# Driver_Motor_opto_bawah.net
KiCad netlist of a schematic drawn in EAGLE
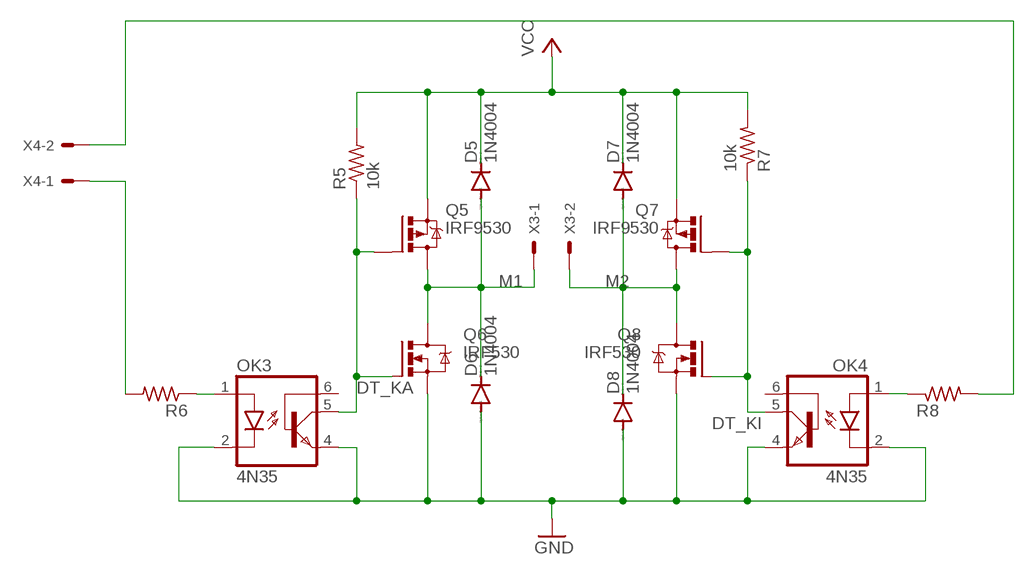
[diagram p0: schematic, sheet 1]

(export (version "E")
  (design (tool "Eeschema 10.0.6"))
  (components
    (comp (ref "D5")
      (value "1N4004")
      (footprint "eagle-import:DO41-10")
      (libsource (lib "eagle-import") (part "1N4004"))
    )
    (comp (ref "D6")
      (value "1N4004")
      (footprint "eagle-import:DO41-10")
      (libsource (lib "eagle-import") (part "1N4004"))
    )
    (comp (ref "D7")
      (value "1N4004")
      (footprint "eagle-import:DO41-10")
      (libsource (lib "eagle-import") (part "1N4004"))
    )
    (comp (ref "D8")
      (value "1N4004")
      (footprint "eagle-import:DO41-10")
      (libsource (lib "eagle-import") (part "1N4004"))
    )
    (comp (ref "OK3")
      (value "4N35")
      (footprint "eagle-import:DIL06")
      (fields (field (name "MF") "FAIRCHILD SEMICONDUCTOR"))
      (libsource (lib "eagle-import") (part "4N35"))
    )
    (comp (ref "OK4")
      (value "4N35")
      (footprint "eagle-import:DIL06")
      (fields (field (name "MF") "FAIRCHILD SEMICONDUCTOR"))
      (libsource (lib "eagle-import") (part "4N35"))
    )
    (comp (ref "Q5")
      (value "IRF9530")
      (footprint "eagle-import:TO220BV")
      (libsource (lib "eagle-import") (part "IRF9530"))
    )
    (comp (ref "Q6")
      (value "IRF530")
      (footprint "eagle-import:TO220BV")
      (libsource (lib "eagle-import") (part "IRF530"))
    )
    (comp (ref "Q7")
      (value "IRF9530")
      (footprint "eagle-import:TO220BV")
      (libsource (lib "eagle-import") (part "IRF9530"))
    )
    (comp (ref "Q8")
      (value "IRF530")
      (footprint "eagle-import:TO220BV")
      (libsource (lib "eagle-import") (part "IRF530"))
    )
    (comp (ref "R5")
      (value "10k")
      (footprint "eagle-import:0207_10")
      (libsource (lib "eagle-import") (part "R-US_0207/10"))
    )
    (comp (ref "R6")
      (value "R-US_0207/10")
      (footprint "eagle-import:0207_10")
      (libsource (lib "eagle-import") (part "R-US_0207/10"))
    )
    (comp (ref "R7")
      (value "10k")
      (footprint "eagle-import:0207_10")
      (libsource (lib "eagle-import") (part "R-US_0207/10"))
    )
    (comp (ref "R8")
      (value "R-US_0207/10")
      (footprint "eagle-import:0207_10")
      (libsource (lib "eagle-import") (part "R-US_0207/10"))
    )
    (comp (ref "X3")
      (value "22-23-2021")
      (footprint "eagle-import:22-23-2021")
      (fields (field (name "MF") "MOLEX"))
      (libsource (lib "eagle-import") (part "22-23-2021"))
    )
    (comp (ref "X4")
      (value "22-23-2021")
      (footprint "eagle-import:22-23-2021")
      (fields (field (name "MF") "MOLEX"))
      (libsource (lib "eagle-import") (part "22-23-2021"))
    )
  )
  (nets
    (net (code "1") (name "/DT_KA") (class "Default")
      (node (ref "OK3") (pin "5") (pinfunction "COL_5") (pintype "passive"))
      (node (ref "Q5") (pin "G") (pinfunction "G_G") (pintype "passive"))
      (node (ref "Q6") (pin "G") (pinfunction "G_G") (pintype "passive"))
      (node (ref "R5") (pin "1") (pinfunction "1_1") (pintype "passive"))
    )
    (net (code "2") (name "/DT_KI") (class "Default")
      (node (ref "OK4") (pin "5") (pinfunction "COL_5") (pintype "passive"))
      (node (ref "Q7") (pin "G") (pinfunction "G_G") (pintype "passive"))
      (node (ref "Q8") (pin "G") (pinfunction "G_G") (pintype "passive"))
      (node (ref "R7") (pin "1") (pinfunction "1_1") (pintype "passive"))
    )
    (net (code "3") (name "/M1") (class "Default")
      (node (ref "D5") (pin "A") (pinfunction "A_A") (pintype "passive"))
      (node (ref "D6") (pin "C") (pinfunction "C_C") (pintype "passive"))
      (node (ref "Q5") (pin "D") (pinfunction "D_D") (pintype "passive"))
      (node (ref "Q6") (pin "D") (pinfunction "D_D") (pintype "passive"))
      (node (ref "X3") (pin "1") (pinfunction "S_1") (pintype "passive"))
    )
    (net (code "4") (name "/M2") (class "Default")
      (node (ref "D7") (pin "A") (pinfunction "A_A") (pintype "passive"))
      (node (ref "D8") (pin "C") (pinfunction "C_C") (pintype "passive"))
      (node (ref "Q7") (pin "D") (pinfunction "D_D") (pintype "passive"))
      (node (ref "Q8") (pin "D") (pinfunction "D_D") (pintype "passive"))
      (node (ref "X3") (pin "2") (pinfunction "S_2") (pintype "passive"))
    )
    (net (code "5") (name "GND") (class "Default")
      (node (ref "D6") (pin "A") (pinfunction "A_A") (pintype "passive"))
      (node (ref "D8") (pin "A") (pinfunction "A_A") (pintype "passive"))
      (node (ref "OK3") (pin "2") (pinfunction "C_2") (pintype "passive"))
      (node (ref "OK3") (pin "4") (pinfunction "EMI_4") (pintype "passive"))
      (node (ref "OK4") (pin "2") (pinfunction "C_2") (pintype "passive"))
      (node (ref "OK4") (pin "4") (pinfunction "EMI_4") (pintype "passive"))
      (node (ref "Q6") (pin "S") (pinfunction "S_S") (pintype "passive"))
      (node (ref "Q8") (pin "S") (pinfunction "S_S") (pintype "passive"))
    )
    (net (code "6") (name "Net-(OK3-A)") (class "Default")
      (node (ref "OK3") (pin "1") (pinfunction "A_1") (pintype "passive"))
      (node (ref "R6") (pin "1") (pinfunction "1_1") (pintype "passive"))
    )
    (net (code "7") (name "Net-(OK4-A)") (class "Default")
      (node (ref "OK4") (pin "1") (pinfunction "A_1") (pintype "passive"))
      (node (ref "R8") (pin "1") (pinfunction "1_1") (pintype "passive"))
    )
    (net (code "8") (name "Net-(X4A-S)") (class "Default")
      (node (ref "R6") (pin "2") (pinfunction "2_2") (pintype "passive"))
      (node (ref "X4") (pin "1") (pinfunction "S_1") (pintype "passive"))
    )
    (net (code "9") (name "Net-(X4B-S)") (class "Default")
      (node (ref "R8") (pin "2") (pinfunction "2_2") (pintype "passive"))
      (node (ref "X4") (pin "2") (pinfunction "S_2") (pintype "passive"))
    )
    (net (code "10") (name "VCC") (class "Default")
      (node (ref "D5") (pin "C") (pinfunction "C_C") (pintype "passive"))
      (node (ref "D7") (pin "C") (pinfunction "C_C") (pintype "passive"))
      (node (ref "Q5") (pin "S") (pinfunction "S_S") (pintype "passive"))
      (node (ref "Q7") (pin "S") (pinfunction "S_S") (pintype "passive"))
      (node (ref "R5") (pin "2") (pinfunction "2_2") (pintype "passive"))
      (node (ref "R7") (pin "2") (pinfunction "2_2") (pintype "passive"))
    )
    (net (code "11") (name "unconnected-(OK3-BAS-Pad6)") (class "Default")
      (node (ref "OK3") (pin "6") (pinfunction "BAS_6") (pintype "passive"))
    )
    (net (code "12") (name "unconnected-(OK4-BAS-Pad6)") (class "Default")
      (node (ref "OK4") (pin "6") (pinfunction "BAS_6") (pintype "passive"))
    )
  )
)
